# MainBoard.net
KiCad netlist of a schematic drawn in EAGLE
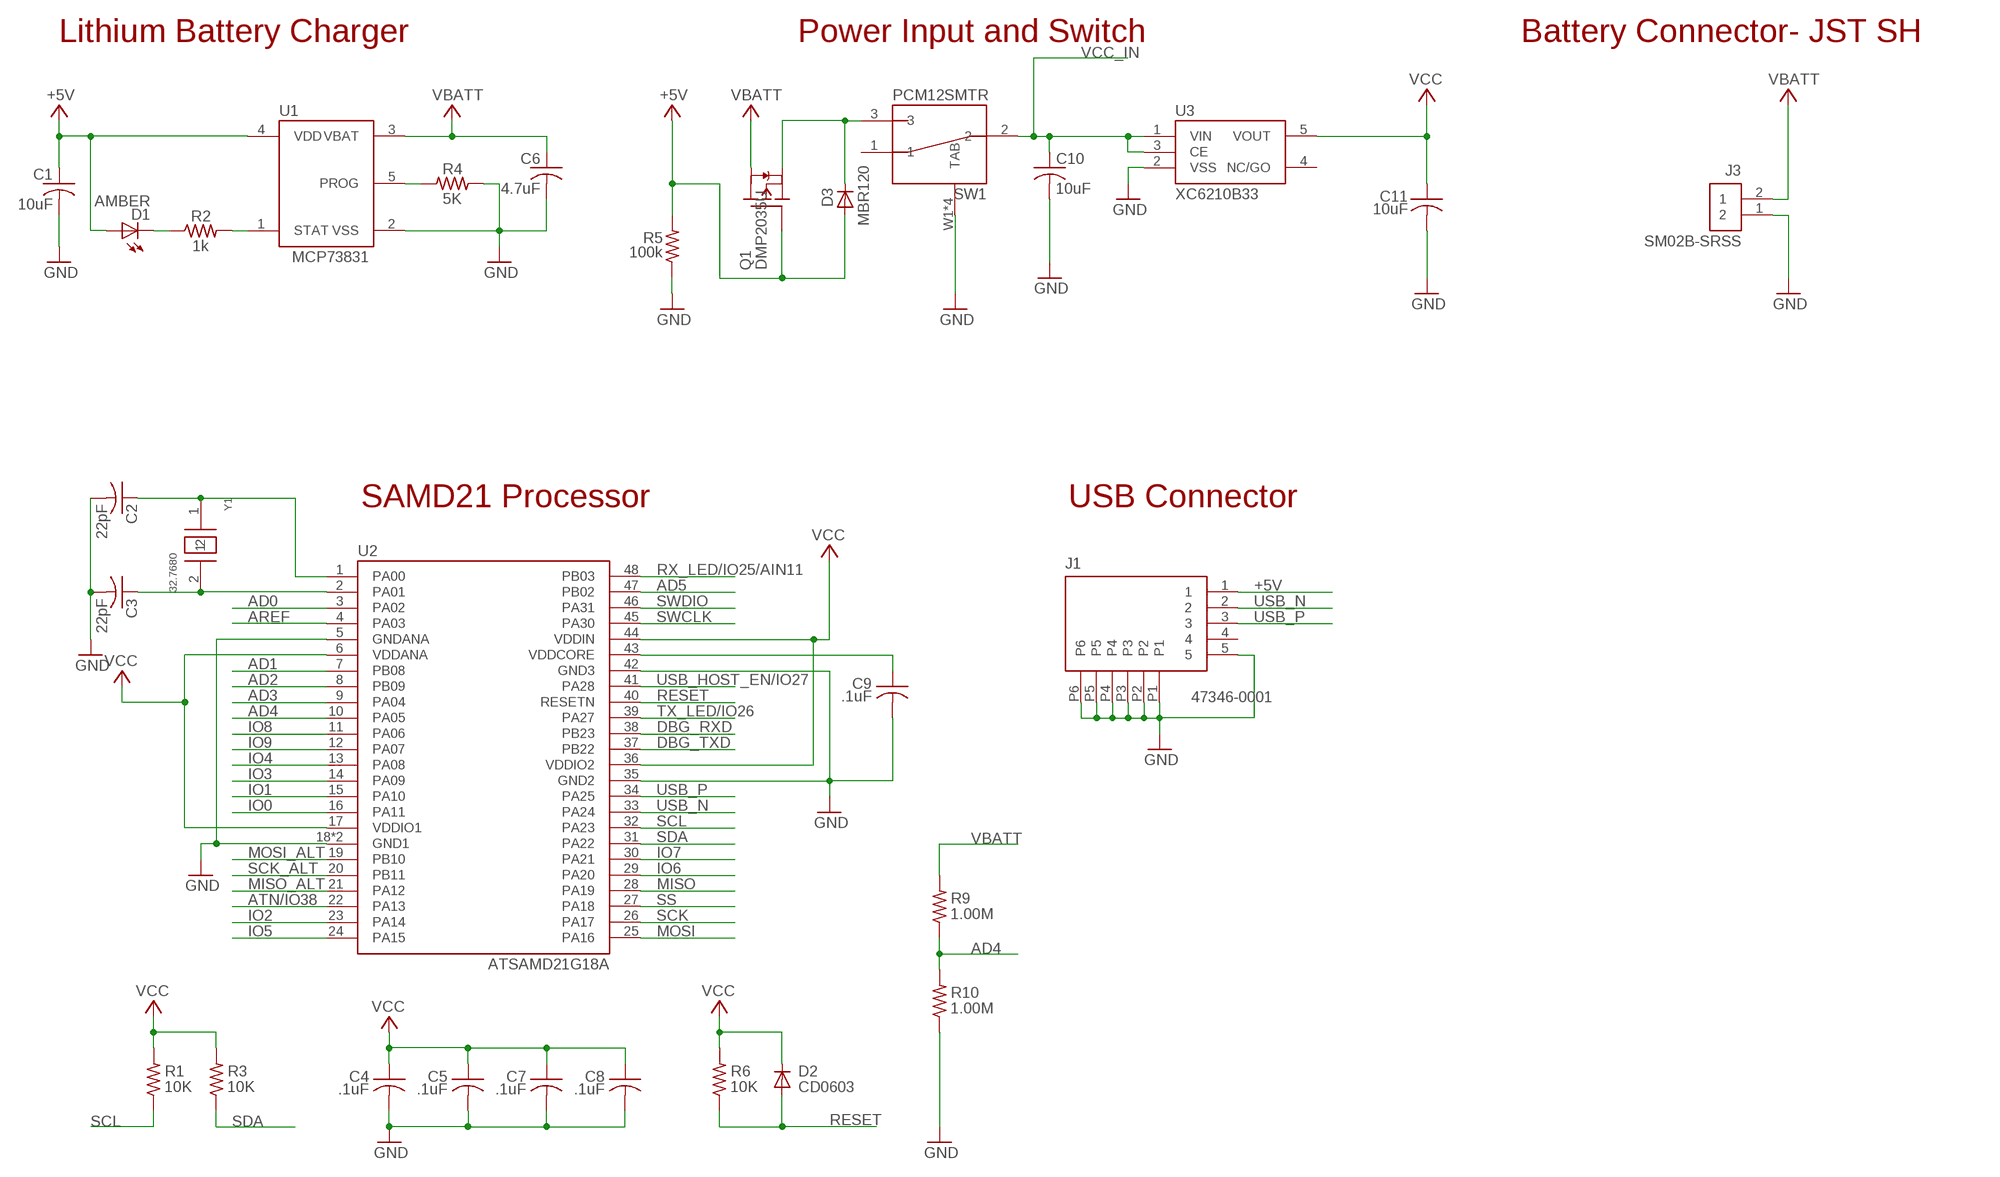
[diagram p0: schematic, sheet 1]

(export (version "E")
  (design (tool "Eeschema 10.0.6"))
  (components
    (comp (ref "C1")
      (value "10uF")
      (footprint "eagle-import:C0603")
      (fields (field (name "PARTNO") "AS-ITM-00002") (field (name "PARTNO_1") "AS-ITM-00002"))
      (libsource (lib "eagle-import") (part "AS-ITM-00002"))
    )
    (comp (ref "C2")
      (value "22pF")
      (footprint "eagle-import:C0402")
      (fields (field (name "PARTNO") "AS-ITM-00211") (field (name "PARTNO_1") "AS-ITM-00211"))
      (libsource (lib "eagle-import") (part "AS-ITM-00211"))
    )
    (comp (ref "C3")
      (value "22pF")
      (footprint "eagle-import:C0402")
      (fields (field (name "PARTNO") "AS-ITM-00211") (field (name "PARTNO_1") "AS-ITM-00211"))
      (libsource (lib "eagle-import") (part "AS-ITM-00211"))
    )
    (comp (ref "C4")
      (value ".1uF")
      (footprint "eagle-import:C0402")
      (fields (field (name "PARTNO") "AS-ITM-00008") (field (name "PARTNO_1") "AS-ITM-00008"))
      (libsource (lib "eagle-import") (part "AS-ITM-00008"))
    )
    (comp (ref "C5")
      (value ".1uF")
      (footprint "eagle-import:C0402")
      (fields (field (name "PARTNO") "AS-ITM-00008") (field (name "PARTNO_1") "AS-ITM-00008"))
      (libsource (lib "eagle-import") (part "AS-ITM-00008"))
    )
    (comp (ref "C6")
      (value "4.7uF")
      (footprint "eagle-import:C0603")
      (fields (field (name "PARTNO") "AS-ITM-00088") (field (name "PARTNO_1") "AS-ITM-00088"))
      (libsource (lib "eagle-import") (part "AS-ITM-00088"))
    )
    (comp (ref "C7")
      (value ".1uF")
      (footprint "eagle-import:C0402")
      (fields (field (name "PARTNO") "AS-ITM-00008") (field (name "PARTNO_1") "AS-ITM-00008"))
      (libsource (lib "eagle-import") (part "AS-ITM-00008"))
    )
    (comp (ref "C8")
      (value ".1uF")
      (footprint "eagle-import:C0402")
      (fields (field (name "PARTNO") "AS-ITM-00008") (field (name "PARTNO_1") "AS-ITM-00008"))
      (libsource (lib "eagle-import") (part "AS-ITM-00008"))
    )
    (comp (ref "C9")
      (value ".1uF")
      (footprint "eagle-import:C0402")
      (fields (field (name "PARTNO") "AS-ITM-00008") (field (name "PARTNO_1") "AS-ITM-00008"))
      (libsource (lib "eagle-import") (part "AS-ITM-00008"))
    )
    (comp (ref "C10")
      (value "10uF")
      (footprint "eagle-import:C0805")
      (fields (field (name "PARTNO") "AS-ITM-00045") (field (name "PARTNO_1") "AS-ITM-00045"))
      (libsource (lib "eagle-import") (part "AS-ITM-00045"))
    )
    (comp (ref "C11")
      (value "10uF")
      (footprint "eagle-import:C0603")
      (fields (field (name "PARTNO") "AS-ITM-00002") (field (name "PARTNO_1") "AS-ITM-00002"))
      (libsource (lib "eagle-import") (part "AS-ITM-00002"))
    )
    (comp (ref "D1")
      (value "AMBER")
      (footprint "eagle-import:LNJ_LED")
      (fields (field (name "PARTNO") "AS-ITM-00026") (field (name "PARTNO_1") "AS-ITM-00026"))
      (libsource (lib "eagle-import") (part "AS-ITM-00026"))
    )
    (comp (ref "D2")
      (value "CD0603")
      (footprint "eagle-import:0603")
      (fields (field (name "PARTNO") "AS-ITM-00009") (field (name "PARTNO_1") "AS-ITM-00009"))
      (libsource (lib "eagle-import") (part "AS-ITM-00009"))
    )
    (comp (ref "D3")
      (value "MBR120")
      (footprint "eagle-import:SOD-123FL")
      (fields (field (name "PARTNO") "AS-ITM-00111"))
      (libsource (lib "eagle-import") (part "AS-ITM-00111"))
    )
    (comp (ref "J1")
      (value "47346-0001")
      (footprint "eagle-import:MICRO_USB")
      (fields (field (name "PARTNO") "AS-ITM-00021"))
      (libsource (lib "eagle-import") (part "AS-ITM-00021"))
    )
    (comp (ref "J3")
      (value "SM02B-SRSS")
      (footprint "eagle-import:JST_SH_2X1")
      (fields (field (name "PARTNO") "AS-ITM-00231"))
      (libsource (lib "eagle-import") (part "AS-ITM-00231"))
    )
    (comp (ref "Q1")
      (value "DMP2035U")
      (footprint "eagle-import:SOT23")
      (fields (field (name "PARTNO") "AS-ITM-00024"))
      (libsource (lib "eagle-import") (part "AS-ITM-00024"))
    )
    (comp (ref "R1")
      (value "10K")
      (footprint "eagle-import:0402")
      (fields (field (name "PARTNO") "AS-ITM-00032") (field (name "PARTNO_1") "AS-ITM-00032"))
      (libsource (lib "eagle-import") (part "AS-ITM-00032"))
    )
    (comp (ref "R2")
      (value "1k")
      (footprint "eagle-import:0402")
      (fields (field (name "PARTNO") "AS-ITM-00003") (field (name "PARTNO_1") "AS-ITM-00003"))
      (libsource (lib "eagle-import") (part "AS-ITM-00003"))
    )
    (comp (ref "R3")
      (value "10K")
      (footprint "eagle-import:0402")
      (fields (field (name "PARTNO") "AS-ITM-00032") (field (name "PARTNO_1") "AS-ITM-00032"))
      (libsource (lib "eagle-import") (part "AS-ITM-00032"))
    )
    (comp (ref "R4")
      (value "5K")
      (footprint "eagle-import:0402")
      (fields (field (name "PARTNO") "AS-ITM-00289"))
      (libsource (lib "eagle-import") (part "AS-ITM-00289"))
    )
    (comp (ref "R5")
      (value "100k")
      (footprint "eagle-import:0402")
      (fields (field (name "PARTNO") "AS-ITM-00004") (field (name "PARTNO_1") "AS-ITM-00004"))
      (libsource (lib "eagle-import") (part "AS-ITM-00004"))
    )
    (comp (ref "R6")
      (value "10K")
      (footprint "eagle-import:0402")
      (fields (field (name "PARTNO") "AS-ITM-00032") (field (name "PARTNO_1") "AS-ITM-00032"))
      (libsource (lib "eagle-import") (part "AS-ITM-00032"))
    )
    (comp (ref "R9")
      (value "1.00M")
      (footprint "eagle-import:0402")
      (fields (field (name "PARTNO") "AS-ITM-00005") (field (name "PARTNO_1") "AS-ITM-00005"))
      (libsource (lib "eagle-import") (part "AS-ITM-00005"))
    )
    (comp (ref "R10")
      (value "1.00M")
      (footprint "eagle-import:0402")
      (fields (field (name "PARTNO") "AS-ITM-00005") (field (name "PARTNO_1") "AS-ITM-00005"))
      (libsource (lib "eagle-import") (part "AS-ITM-00005"))
    )
    (comp (ref "SW1")
      (value "PCM12SMTR")
      (footprint "eagle-import:PCM12SMTR")
      (fields (field (name "PARTNO") "AS-ITM-00220"))
      (libsource (lib "eagle-import") (part "AS-ITM-00220"))
    )
    (comp (ref "U1")
      (value "MCP73831")
      (footprint "eagle-import:SOT-23")
      (fields (field (name "PARTNO") "AS-ITM-00136"))
      (libsource (lib "eagle-import") (part "AS-ITM-00136"))
    )
    (comp (ref "U2")
      (value "ATSAMD21G18A")
      (footprint "eagle-import:QFN48")
      (fields (field (name "PARTNO") "AS-ITM-00273") (field (name "PARTNO_1") "AS-ITM-00273"))
      (libsource (lib "eagle-import") (part "AS-ITM-00273"))
    )
    (comp (ref "U3")
      (value "XC6210B33")
      (footprint "eagle-import:SOT-25")
      (fields (field (name "PARTNO") "AS-ITM-00046"))
      (libsource (lib "eagle-import") (part "AS-ITM-00046"))
    )
    (comp (ref "Y1")
      (value "32.7680")
      (footprint "eagle-import:ABS06")
      (fields (field (name "PARTNO") "AS-ITM-00279") (field (name "PARTNO_1") "AS-ITM-00279"))
      (libsource (lib "eagle-import") (part "AS-ITM-00279"))
    )
  )
  (nets
    (net (code "1") (name "+5V") (class "Default")
      (node (ref "C1") (pin "1") (pinfunction "1_1") (pintype "passive"))
      (node (ref "D1") (pin "A") (pinfunction "A_A") (pintype "passive"))
      (node (ref "D3") (pin "A") (pinfunction "A_A") (pintype "passive"))
      (node (ref "J1") (pin "1") (pinfunction "1_1") (pintype "bidirectional"))
      (node (ref "Q1") (pin "B") (pinfunction "G_B") (pintype "passive"))
      (node (ref "R5") (pin "2") (pinfunction "2_2") (pintype "passive"))
      (node (ref "U1") (pin "4") (pinfunction "VDD_4") (pintype "bidirectional"))
    )
    (net (code "2") (name "/AD0") (class "Default")
      (node (ref "U2") (pin "3") (pinfunction "PA02_3") (pintype "bidirectional"))
    )
    (net (code "3") (name "/AD1") (class "Default")
      (node (ref "U2") (pin "7") (pinfunction "PB08_7") (pintype "bidirectional"))
    )
    (net (code "4") (name "/AD2") (class "Default")
      (node (ref "U2") (pin "8") (pinfunction "PB09_8") (pintype "bidirectional"))
    )
    (net (code "5") (name "/AD3") (class "Default")
      (node (ref "U2") (pin "9") (pinfunction "PA04_9") (pintype "bidirectional"))
    )
    (net (code "6") (name "/AD4") (class "Default")
      (node (ref "R10") (pin "2") (pinfunction "2_2") (pintype "passive"))
      (node (ref "R9") (pin "1") (pinfunction "1_1") (pintype "passive"))
      (node (ref "U2") (pin "10") (pinfunction "PA05_10") (pintype "bidirectional"))
    )
    (net (code "7") (name "/AD5") (class "Default")
      (node (ref "U2") (pin "47") (pinfunction "PB02_47") (pintype "bidirectional"))
    )
    (net (code "8") (name "/AREF") (class "Default")
      (node (ref "U2") (pin "4") (pinfunction "PA03_4") (pintype "bidirectional"))
    )
    (net (code "9") (name "/ATN{slash}IO38") (class "Default")
      (node (ref "U2") (pin "22") (pinfunction "PA13_22") (pintype "bidirectional"))
    )
    (net (code "10") (name "/DBG_RXD") (class "Default")
      (node (ref "U2") (pin "38") (pinfunction "PB23_38") (pintype "bidirectional"))
    )
    (net (code "11") (name "/DBG_TXD") (class "Default")
      (node (ref "U2") (pin "37") (pinfunction "PB22_37") (pintype "bidirectional"))
    )
    (net (code "12") (name "/IO0") (class "Default")
      (node (ref "U2") (pin "16") (pinfunction "PA11_16") (pintype "bidirectional"))
    )
    (net (code "13") (name "/IO1") (class "Default")
      (node (ref "U2") (pin "15") (pinfunction "PA10_15") (pintype "bidirectional"))
    )
    (net (code "14") (name "/IO2") (class "Default")
      (node (ref "U2") (pin "23") (pinfunction "PA14_23") (pintype "bidirectional"))
    )
    (net (code "15") (name "/IO3") (class "Default")
      (node (ref "U2") (pin "14") (pinfunction "PA09_14") (pintype "bidirectional"))
    )
    (net (code "16") (name "/IO4") (class "Default")
      (node (ref "U2") (pin "13") (pinfunction "PA08_13") (pintype "bidirectional"))
    )
    (net (code "17") (name "/IO5") (class "Default")
      (node (ref "U2") (pin "24") (pinfunction "PA15_24") (pintype "bidirectional"))
    )
    (net (code "18") (name "/IO6") (class "Default")
      (node (ref "U2") (pin "29") (pinfunction "PA20_29") (pintype "bidirectional"))
    )
    (net (code "19") (name "/IO7") (class "Default")
      (node (ref "U2") (pin "30") (pinfunction "PA21_30") (pintype "bidirectional"))
    )
    (net (code "20") (name "/IO8") (class "Default")
      (node (ref "U2") (pin "11") (pinfunction "PA06_11") (pintype "bidirectional"))
    )
    (net (code "21") (name "/IO9") (class "Default")
      (node (ref "U2") (pin "12") (pinfunction "PA07_12") (pintype "bidirectional"))
    )
    (net (code "22") (name "/MISO") (class "Default")
      (node (ref "U2") (pin "28") (pinfunction "PA19_28") (pintype "bidirectional"))
    )
    (net (code "23") (name "/MISO_ALT") (class "Default")
      (node (ref "U2") (pin "21") (pinfunction "PA12_21") (pintype "bidirectional"))
    )
    (net (code "24") (name "/MOSI") (class "Default")
      (node (ref "U2") (pin "25") (pinfunction "PA16_25") (pintype "bidirectional"))
    )
    (net (code "25") (name "/MOSI_ALT") (class "Default")
      (node (ref "U2") (pin "19") (pinfunction "PB10_19") (pintype "bidirectional"))
    )
    (net (code "26") (name "/RESET") (class "Default")
      (node (ref "D2") (pin "A") (pinfunction "A_A") (pintype "passive"))
      (node (ref "R6") (pin "1") (pinfunction "1_1") (pintype "passive"))
      (node (ref "U2") (pin "40") (pinfunction "RESETN_40") (pintype "bidirectional"))
    )
    (net (code "27") (name "/RX_LED{slash}IO25{slash}AIN11") (class "Default")
      (node (ref "U2") (pin "48") (pinfunction "PB03_48") (pintype "bidirectional"))
    )
    (net (code "28") (name "/SCK") (class "Default")
      (node (ref "U2") (pin "26") (pinfunction "PA17_26") (pintype "bidirectional"))
    )
    (net (code "29") (name "/SCK_ALT") (class "Default")
      (node (ref "U2") (pin "20") (pinfunction "PB11_20") (pintype "bidirectional"))
    )
    (net (code "30") (name "/SCL") (class "Default")
      (node (ref "R1") (pin "1") (pinfunction "1_1") (pintype "passive"))
      (node (ref "U2") (pin "32") (pinfunction "PA23_32") (pintype "bidirectional"))
    )
    (net (code "31") (name "/SDA") (class "Default")
      (node (ref "R3") (pin "1") (pinfunction "1_1") (pintype "passive"))
      (node (ref "U2") (pin "31") (pinfunction "PA22_31") (pintype "bidirectional"))
    )
    (net (code "32") (name "/SS") (class "Default")
      (node (ref "U2") (pin "27") (pinfunction "PA18_27") (pintype "bidirectional"))
    )
    (net (code "33") (name "/SWCLK") (class "Default")
      (node (ref "U2") (pin "45") (pinfunction "PA30_45") (pintype "bidirectional"))
    )
    (net (code "34") (name "/SWDIO") (class "Default")
      (node (ref "U2") (pin "46") (pinfunction "PA31_46") (pintype "bidirectional"))
    )
    (net (code "35") (name "/TX_LED{slash}IO26") (class "Default")
      (node (ref "U2") (pin "39") (pinfunction "PA27_39") (pintype "bidirectional"))
    )
    (net (code "36") (name "/USB_HOST_EN{slash}IO27") (class "Default")
      (node (ref "U2") (pin "41") (pinfunction "PA28_41") (pintype "bidirectional"))
    )
    (net (code "37") (name "/USB_N") (class "Default")
      (node (ref "J1") (pin "2") (pinfunction "2_2") (pintype "bidirectional"))
      (node (ref "U2") (pin "33") (pinfunction "PA24_33") (pintype "bidirectional"))
    )
    (net (code "38") (name "/USB_P") (class "Default")
      (node (ref "J1") (pin "3") (pinfunction "3_3") (pintype "bidirectional"))
      (node (ref "U2") (pin "34") (pinfunction "PA25_34") (pintype "bidirectional"))
    )
    (net (code "39") (name "/VCC_IN") (class "Default")
      (node (ref "C10") (pin "1") (pinfunction "1_1") (pintype "passive"))
      (node (ref "SW1") (pin "2") (pinfunction "2_2") (pintype "bidirectional"))
      (node (ref "U3") (pin "1") (pinfunction "VIN_1") (pintype "bidirectional"))
      (node (ref "U3") (pin "3") (pinfunction "CE_3") (pintype "bidirectional"))
    )
    (net (code "40") (name "GND") (class "Default")
      (node (ref "C1") (pin "2") (pinfunction "2_2") (pintype "passive"))
      (node (ref "C10") (pin "2") (pinfunction "2_2") (pintype "passive"))
      (node (ref "C11") (pin "2") (pinfunction "2_2") (pintype "passive"))
      (node (ref "C2") (pin "2") (pinfunction "2_2") (pintype "passive"))
      (node (ref "C3") (pin "2") (pinfunction "2_2") (pintype "passive"))
      (node (ref "C4") (pin "2") (pinfunction "2_2") (pintype "passive"))
      (node (ref "C5") (pin "2") (pinfunction "2_2") (pintype "passive"))
      (node (ref "C6") (pin "2") (pinfunction "2_2") (pintype "passive"))
      (node (ref "C7") (pin "2") (pinfunction "2_2") (pintype "passive"))
      (node (ref "C8") (pin "2") (pinfunction "2_2") (pintype "passive"))
      (node (ref "C9") (pin "2") (pinfunction "2_2") (pintype "passive"))
      (node (ref "J1") (pin "5") (pinfunction "5_5") (pintype "bidirectional"))
      (node (ref "J1") (pin "P1") (pinfunction "P1_P1") (pintype "bidirectional"))
      (node (ref "J1") (pin "P2") (pinfunction "P2_P2") (pintype "bidirectional"))
      (node (ref "J1") (pin "P3") (pinfunction "P3_P3") (pintype "bidirectional"))
      (node (ref "J1") (pin "P4") (pinfunction "P4_P4") (pintype "bidirectional"))
      (node (ref "J1") (pin "P5") (pinfunction "P5_P5") (pintype "bidirectional"))
      (node (ref "J1") (pin "P6") (pinfunction "P6_P6") (pintype "bidirectional"))
      (node (ref "J3") (pin "1") (pinfunction "2_1") (pintype "bidirectional"))
      (node (ref "R10") (pin "1") (pinfunction "1_1") (pintype "passive"))
      (node (ref "R4") (pin "2") (pinfunction "2_2") (pintype "passive"))
      (node (ref "R5") (pin "1") (pinfunction "1_1") (pintype "passive"))
      (node (ref "SW1") (pin "W1") (pinfunction "TAB_W1") (pintype "bidirectional"))
      (node (ref "SW1") (pin "W2") (pinfunction "TAB_W2") (pintype "bidirectional"))
      (node (ref "SW1") (pin "W3") (pinfunction "TAB_W3") (pintype "bidirectional"))
      (node (ref "SW1") (pin "W4") (pinfunction "TAB_W4") (pintype "bidirectional"))
      (node (ref "U1") (pin "2") (pinfunction "VSS_2") (pintype "bidirectional"))
      (node (ref "U2") (pin "18") (pinfunction "GND1_18") (pintype "bidirectional"))
      (node (ref "U2") (pin "35") (pinfunction "GND2_35") (pintype "bidirectional"))
      (node (ref "U2") (pin "42") (pinfunction "GND3_42") (pintype "bidirectional"))
      (node (ref "U2") (pin "5") (pinfunction "GNDANA_5") (pintype "bidirectional"))
      (node (ref "U2") (pin "EXP") (pinfunction "GND1_EXP") (pintype "bidirectional"))
      (node (ref "U3") (pin "2") (pinfunction "VSS_2") (pintype "power_in"))
    )
    (net (code "41") (name "Net-(D1-PadC)") (class "Default")
      (node (ref "D1") (pin "C") (pinfunction "C_C") (pintype "passive"))
      (node (ref "R2") (pin "1") (pinfunction "1_1") (pintype "passive"))
    )
    (net (code "42") (name "Net-(Q1-S)") (class "Default")
      (node (ref "D3") (pin "C") (pinfunction "C_C") (pintype "passive"))
      (node (ref "Q1") (pin "E") (pinfunction "S_E") (pintype "passive"))
      (node (ref "SW1") (pin "3") (pinfunction "3_3") (pintype "bidirectional"))
    )
    (net (code "43") (name "Net-(U1-PROG)") (class "Default")
      (node (ref "R4") (pin "1") (pinfunction "1_1") (pintype "passive"))
      (node (ref "U1") (pin "5") (pinfunction "PROG_5") (pintype "bidirectional"))
    )
    (net (code "44") (name "Net-(U1-STAT)") (class "Default")
      (node (ref "R2") (pin "2") (pinfunction "2_2") (pintype "passive"))
      (node (ref "U1") (pin "1") (pinfunction "STAT_1") (pintype "bidirectional"))
    )
    (net (code "45") (name "Net-(U2-PA00)") (class "Default")
      (node (ref "C2") (pin "1") (pinfunction "1_1") (pintype "passive"))
      (node (ref "U2") (pin "1") (pinfunction "PA00_1") (pintype "bidirectional"))
      (node (ref "Y1") (pin "1") (pinfunction "1_1") (pintype "bidirectional"))
    )
    (net (code "46") (name "Net-(U2-PA01)") (class "Default")
      (node (ref "C3") (pin "1") (pinfunction "1_1") (pintype "passive"))
      (node (ref "U2") (pin "2") (pinfunction "PA01_2") (pintype "bidirectional"))
      (node (ref "Y1") (pin "2") (pinfunction "2_2") (pintype "bidirectional"))
    )
    (net (code "47") (name "Net-(U2-VDDCORE)") (class "Default")
      (node (ref "C9") (pin "1") (pinfunction "1_1") (pintype "passive"))
      (node (ref "U2") (pin "43") (pinfunction "VDDCORE_43") (pintype "bidirectional"))
    )
    (net (code "48") (name "VBATT") (class "Default")
      (node (ref "C6") (pin "1") (pinfunction "1_1") (pintype "passive"))
      (node (ref "J3") (pin "2") (pinfunction "1_2") (pintype "bidirectional"))
      (node (ref "Q1") (pin "C") (pinfunction "D_C") (pintype "passive"))
      (node (ref "R9") (pin "2") (pinfunction "2_2") (pintype "passive"))
      (node (ref "U1") (pin "3") (pinfunction "VBAT_3") (pintype "bidirectional"))
    )
    (net (code "49") (name "VCC") (class "Default")
      (node (ref "C11") (pin "1") (pinfunction "1_1") (pintype "passive"))
      (node (ref "C4") (pin "1") (pinfunction "1_1") (pintype "passive"))
      (node (ref "C5") (pin "1") (pinfunction "1_1") (pintype "passive"))
      (node (ref "C7") (pin "1") (pinfunction "1_1") (pintype "passive"))
      (node (ref "C8") (pin "1") (pinfunction "1_1") (pintype "passive"))
      (node (ref "D2") (pin "C") (pinfunction "C_C") (pintype "passive"))
      (node (ref "R1") (pin "2") (pinfunction "2_2") (pintype "passive"))
      (node (ref "R3") (pin "2") (pinfunction "2_2") (pintype "passive"))
      (node (ref "R6") (pin "2") (pinfunction "2_2") (pintype "passive"))
      (node (ref "U2") (pin "17") (pinfunction "VDDIO1_17") (pintype "bidirectional"))
      (node (ref "U2") (pin "36") (pinfunction "VDDIO2_36") (pintype "bidirectional"))
      (node (ref "U2") (pin "44") (pinfunction "VDDIN_44") (pintype "bidirectional"))
      (node (ref "U2") (pin "6") (pinfunction "VDDANA_6") (pintype "bidirectional"))
      (node (ref "U3") (pin "5") (pinfunction "VOUT_5") (pintype "bidirectional"))
    )
    (net (code "50") (name "unconnected-(J1-Pad4)") (class "Default")
      (node (ref "J1") (pin "4") (pinfunction "4_4") (pintype "bidirectional"))
    )
    (net (code "51") (name "unconnected-(SW1-Pad1)") (class "Default")
      (node (ref "SW1") (pin "1") (pinfunction "1_1") (pintype "bidirectional"))
    )
    (net (code "52") (name "unconnected-(U3-NC{slash}GO-Pad4)") (class "Default")
      (node (ref "U3") (pin "4") (pinfunction "NC/GO_4") (pintype "bidirectional"))
    )
  )
)
